# Test_TG21.net
KiCad netlist of a schematic drawn in Altium Designer
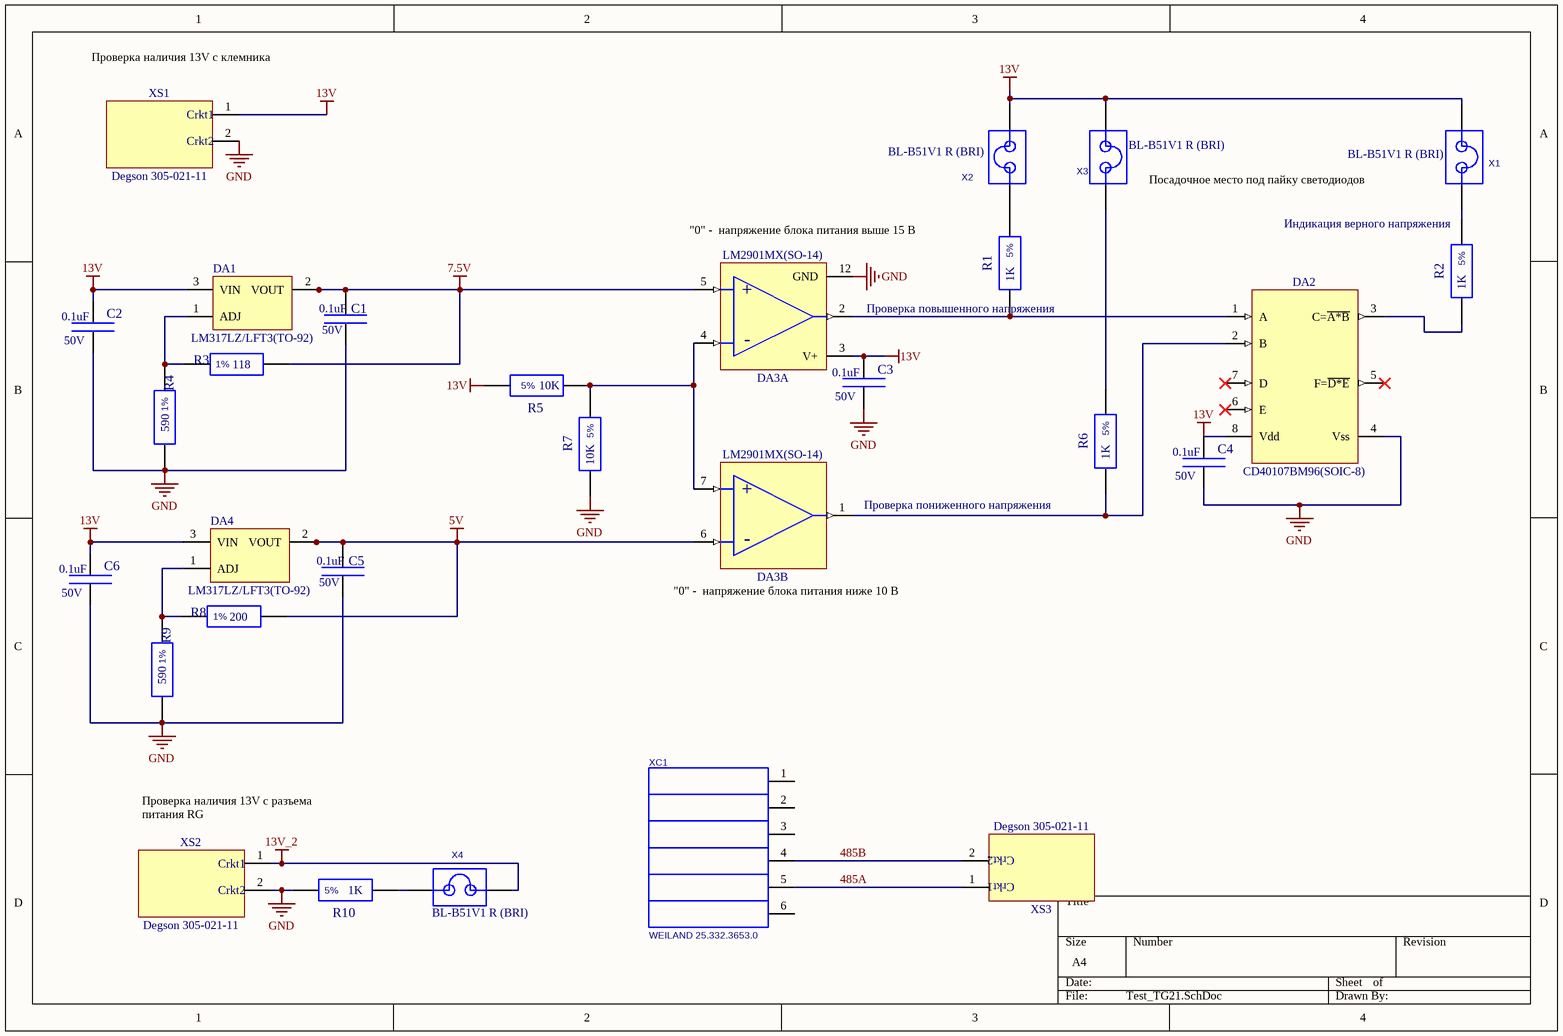
[diagram p0: Test_TG21.SchDoc]

(export (version "E")
  (design (tool "Eeschema 10.0.6"))
  (components
    (comp (ref "C1")
      (value "0.1uF")
      (footprint "CAPC1608X50(0603)")
      (description "C0603")
      (fields (field (name "PARVOLTAGE") "50V") (field (name "Comment") "чип 0603 0.1uF/50V, "))
      (libsource (lib "pass_smd") (part "C0603"))
    )
    (comp (ref "C2")
      (value "0.1uF")
      (footprint "CAPC1608X50(0603)")
      (description "C0603")
      (fields (field (name "PARVOLTAGE") "50V") (field (name "Comment") "чип 0603 0.1uF/50V, "))
      (libsource (lib "pass_smd") (part "C0603"))
    )
    (comp (ref "C3")
      (value "0.1uF")
      (footprint "CAPC1608X50(0603)")
      (description "C0603")
      (fields (field (name "PARVOLTAGE") "50V") (field (name "Comment") "чип 0603 0.1uF/50V, "))
      (libsource (lib "pass_smd") (part "C0603"))
    )
    (comp (ref "C4")
      (value "0.1uF")
      (footprint "CAPC1608X50(0603)")
      (description "C0603")
      (fields (field (name "PARVOLTAGE") "50V") (field (name "Comment") "чип 0603 0.1uF/50V, "))
      (libsource (lib "pass_smd") (part "C0603"))
    )
    (comp (ref "C5")
      (value "0.1uF")
      (footprint "CAPC1608X50(0603)")
      (description "C0603")
      (fields (field (name "PARVOLTAGE") "50V") (field (name "Comment") "чип 0603 0.1uF/50V, "))
      (libsource (lib "pass_smd") (part "C0603"))
    )
    (comp (ref "C6")
      (value "0.1uF")
      (footprint "CAPC1608X50(0603)")
      (description "C0603")
      (fields (field (name "PARVOLTAGE") "50V") (field (name "Comment") "чип 0603 0.1uF/50V, "))
      (libsource (lib "pass_smd") (part "C0603"))
    )
    (comp (ref "DA1")
      (value "LM317LZ/LFT3(TO-92)")
      (footprint "SOT230P700X180-4N(SOT223)_NUM")
      (description "3-Terminal Adjustable Regulator")
      (fields (field (name "CMPPARTNUM") "LM317LZ/LFT3"))
      (libsource (lib "TI") (part "Lm317l-n"))
    )
    (comp (ref "DA2")
      (value "CD40107BM96(SOIC-8)")
      (footprint "SOIC127P600-8N")
      (description "CMOS Dual 2-Input NAND Buffer/Driver")
      (fields (field (name "CMPPARTNUM") "CD40107BM96"))
      (libsource (lib "TI") (part "CD40107B"))
    )
    (comp (ref "DA3")
      (value "LM2901MX(SO-14)")
      (footprint "SOIC127P600X145-14M")
      (fields (field (name "CMPPARTNUM") "LM2901MX"))
      (libsource (lib "TI") (part "LM2901"))
    )
    (comp (ref "DA4")
      (value "LM317LZ/LFT3(TO-92)")
      (footprint "SOT230P700X180-4N(SOT223)_NUM")
      (description "3-Terminal Adjustable Regulator")
      (fields (field (name "CMPPARTNUM") "LM317LZ/LFT3"))
      (libsource (lib "TI") (part "Lm317l-n"))
    )
    (comp (ref "R1")
      (value "1K")
      (footprint "RESC1608X45(0603)")
      (description "R0603")
      (fields (field (name "TOLERANCE") "5%") (field (name "Comment") "чип 0603 1K 5%"))
      (libsource (lib "pass_smd") (part "R0603"))
    )
    (comp (ref "R2")
      (value "1K")
      (footprint "RESC1608X45(0603)")
      (description "R0603")
      (fields (field (name "TOLERANCE") "5%") (field (name "Comment") "чип 0603 1K 5%"))
      (libsource (lib "pass_smd") (part "R0603"))
    )
    (comp (ref "R3")
      (value "118")
      (footprint "RESC1608X45(0603)")
      (description "R0603")
      (fields (field (name "TOLERANCE") "1%") (field (name "Comment") "чип 0603 118 1%"))
      (libsource (lib "pass_smd") (part "R0603"))
    )
    (comp (ref "R4")
      (value "590")
      (footprint "RESC1608X45(0603)")
      (description "R0603")
      (fields (field (name "TOLERANCE") "1%") (field (name "Comment") "чип 0603 590 1%"))
      (libsource (lib "pass_smd") (part "R0603"))
    )
    (comp (ref "R5")
      (value "10K")
      (footprint "RESC1608X45(0603)")
      (description "R0603")
      (fields (field (name "TOLERANCE") "5%") (field (name "Comment") "чип 0603 10K 5%"))
      (libsource (lib "pass_smd") (part "R0603"))
    )
    (comp (ref "R6")
      (value "1K")
      (footprint "RESC1608X45(0603)")
      (description "R0603")
      (fields (field (name "TOLERANCE") "5%") (field (name "Comment") "чип 0603 1K 5%"))
      (libsource (lib "pass_smd") (part "R0603"))
    )
    (comp (ref "R7")
      (value "10K")
      (footprint "RESC1608X45(0603)")
      (description "R0603")
      (fields (field (name "TOLERANCE") "5%") (field (name "Comment") "чип 0603 10K 5%"))
      (libsource (lib "pass_smd") (part "R0603"))
    )
    (comp (ref "R8")
      (value "200")
      (footprint "RESC1608X45(0603)")
      (description "R0603")
      (fields (field (name "TOLERANCE") "1%") (field (name "Comment") "чип 0603 200 1%"))
      (libsource (lib "pass_smd") (part "R0603"))
    )
    (comp (ref "R9")
      (value "590")
      (footprint "RESC1608X45(0603)")
      (description "R0603")
      (fields (field (name "TOLERANCE") "1%") (field (name "Comment") "чип 0603 590 1%"))
      (libsource (lib "pass_smd") (part "R0603"))
    )
    (comp (ref "R10")
      (value "1K")
      (footprint "RESC1608X45(0603)")
      (description "R0603")
      (fields (field (name "TOLERANCE") "5%") (field (name "Comment") "чип 0603 1K 5%"))
      (libsource (lib "pass_smd") (part "R0603"))
    )
    (comp (ref "X1")
      (value "BL-B51V1 R (BRI)")
      (footprint "JMP")
      (description "JMP")
      (libsource (lib "9200mb") (part "JMP"))
    )
    (comp (ref "X2")
      (value "BL-B51V1 R (BRI)")
      (footprint "JMP")
      (description "JMP")
      (libsource (lib "9200mb") (part "JMP"))
    )
    (comp (ref "X3")
      (value "BL-B51V1 R (BRI)")
      (footprint "JMP")
      (description "JMP")
      (libsource (lib "9200mb") (part "JMP"))
    )
    (comp (ref "X4")
      (value "BL-B51V1 R (BRI)")
      (footprint "JMP")
      (description "JMP")
      (libsource (lib "9200mb") (part "JMP"))
    )
    (comp (ref "XC1")
      (value "WEILAND 25.332.3653.0")
      (footprint "WEILAND_25.332.3653.0")
      (description "WEILAND_6PIN_5MM")
      (libsource (lib "connectors") (part "WEILAND_6PIN_5MM"))
    )
    (comp (ref "XS1")
      (value "Degson 305-021-11")
      (footprint "305-021-11")
      (description "Клеммник винтовой, 2-контактный, 5мм, пр мой")
      (fields (field (name "CMPPARTNUM") "305-021-11"))
      (libsource (lib "connectors") (part "305-021-11"))
    )
    (comp (ref "XS2")
      (value "Degson 305-021-11")
      (footprint "305-021-11")
      (description "Клеммник винтовой, 2-контактный, 5мм, пр мой")
      (fields (field (name "CMPPARTNUM") "305-021-11"))
      (libsource (lib "connectors") (part "305-021-11"))
    )
    (comp (ref "XS3")
      (value "Degson 305-021-11")
      (footprint "305-021-11")
      (description "Клеммник винтовой, 2-контактный, 5мм, пр мой")
      (fields (field (name "CMPPARTNUM") "305-021-11"))
      (libsource (lib "") (part "305-021-11_1"))
    )
  )
  (nets
    (net (code "1") (name "/485A") (class "Default")
      (node (ref "XC1") (pin "5") (pinfunction "5_5") (pintype "passive"))
      (node (ref "XS3") (pin "1") (pinfunction "1_1") (pintype "passive"))
    )
    (net (code "2") (name "/485B") (class "Default")
      (node (ref "XC1") (pin "4") (pinfunction "4_4") (pintype "passive"))
      (node (ref "XS3") (pin "2") (pinfunction "2_2") (pintype "passive"))
    )
    (net (code "3") (name "5V") (class "Default")
      (node (ref "C5") (pin "2") (pinfunction "P2_2") (pintype "passive"))
      (node (ref "DA3") (pin "6") (pinfunction "IN-_6") (pintype "input"))
      (node (ref "DA4") (pin "2") (pinfunction "VOUT_2") (pintype "power_in"))
      (node (ref "DA4") (pin "4") (pinfunction "VOUT_4") (pintype "power_in"))
      (node (ref "R8") (pin "1") (pinfunction "1_1") (pintype "passive"))
    )
    (net (code "4") (name "7.5V") (class "Default")
      (node (ref "C1") (pin "2") (pinfunction "P2_2") (pintype "passive"))
      (node (ref "DA1") (pin "2") (pinfunction "VOUT_2") (pintype "power_in"))
      (node (ref "DA1") (pin "4") (pinfunction "VOUT_4") (pintype "power_in"))
      (node (ref "DA3") (pin "5") (pinfunction "IN+_5") (pintype "input"))
      (node (ref "R3") (pin "1") (pinfunction "1_1") (pintype "passive"))
    )
    (net (code "5") (name "13V") (class "Default")
      (node (ref "C2") (pin "2") (pinfunction "P2_2") (pintype "passive"))
      (node (ref "C3") (pin "2") (pinfunction "P2_2") (pintype "passive"))
      (node (ref "C4") (pin "2") (pinfunction "P2_2") (pintype "passive"))
      (node (ref "C6") (pin "2") (pinfunction "P2_2") (pintype "passive"))
      (node (ref "DA1") (pin "3") (pinfunction "VIN_3") (pintype "power_in"))
      (node (ref "DA2") (pin "8") (pinfunction "Vdd_8") (pintype "passive"))
      (node (ref "DA3") (pin "3") (pinfunction "V+_3") (pintype "passive"))
      (node (ref "DA4") (pin "3") (pinfunction "VIN_3") (pintype "power_in"))
      (node (ref "R5") (pin "2") (pinfunction "2_2") (pintype "passive"))
      (node (ref "X1") (pin "1") (pinfunction "1_1") (pintype "passive"))
      (node (ref "X2") (pin "2") (pinfunction "2_2") (pintype "passive"))
      (node (ref "X3") (pin "1") (pinfunction "1_1") (pintype "passive"))
      (node (ref "XS1") (pin "1") (pinfunction "1_1") (pintype "passive"))
    )
    (net (code "6") (name "13V_2") (class "Default")
      (node (ref "X4") (pin "2") (pinfunction "2_2") (pintype "passive"))
      (node (ref "XS2") (pin "1") (pinfunction "1_1") (pintype "passive"))
    )
    (net (code "7") (name "GND") (class "Default")
      (node (ref "C1") (pin "1") (pinfunction "P1_1") (pintype "passive"))
      (node (ref "C2") (pin "1") (pinfunction "P1_1") (pintype "passive"))
      (node (ref "C3") (pin "1") (pinfunction "P1_1") (pintype "passive"))
      (node (ref "C4") (pin "1") (pinfunction "P1_1") (pintype "passive"))
      (node (ref "C5") (pin "1") (pinfunction "P1_1") (pintype "passive"))
      (node (ref "C6") (pin "1") (pinfunction "P1_1") (pintype "passive"))
      (node (ref "DA2") (pin "4") (pinfunction "Vss_4") (pintype "passive"))
      (node (ref "DA3") (pin "12") (pinfunction "GND_12") (pintype "passive"))
      (node (ref "R10") (pin "2") (pinfunction "2_2") (pintype "passive"))
      (node (ref "R4") (pin "1") (pinfunction "1_1") (pintype "passive"))
      (node (ref "R7") (pin "1") (pinfunction "1_1") (pintype "passive"))
      (node (ref "R9") (pin "1") (pinfunction "1_1") (pintype "passive"))
      (node (ref "XS1") (pin "2") (pinfunction "2_2") (pintype "passive"))
      (node (ref "XS2") (pin "2") (pinfunction "2_2") (pintype "passive"))
    )
    (net (code "8") (name "Net-(DA1-ADJ)") (class "Default")
      (node (ref "DA1") (pin "1") (pinfunction "ADJ_1") (pintype "power_in"))
      (node (ref "R3") (pin "2") (pinfunction "2_2") (pintype "passive"))
      (node (ref "R4") (pin "2") (pinfunction "2_2") (pintype "passive"))
    )
    (net (code "9") (name "Net-(DA2-A)") (class "Default")
      (node (ref "DA2") (pin "1") (pinfunction "A_1") (pintype "input"))
      (node (ref "DA3") (pin "2") (pinfunction "Out_2") (pintype "output"))
      (node (ref "R1") (pin "1") (pinfunction "1_1") (pintype "passive"))
    )
    (net (code "10") (name "Net-(DA2-B)") (class "Default")
      (node (ref "DA2") (pin "2") (pinfunction "B_2") (pintype "input"))
      (node (ref "DA3") (pin "1") (pinfunction "Out_1") (pintype "output"))
      (node (ref "R6") (pin "1") (pinfunction "1_1") (pintype "passive"))
    )
    (net (code "11") (name "Net-(DA2-C=~{A*B})") (class "Default")
      (node (ref "DA2") (pin "3") (pinfunction "C=~{A*B}_3") (pintype "output"))
      (node (ref "R2") (pin "1") (pinfunction "1_1") (pintype "passive"))
    )
    (net (code "12") (name "Net-(DA3A-IN-)") (class "Default")
      (node (ref "DA3") (pin "4") (pinfunction "IN-_4") (pintype "input"))
      (node (ref "DA3") (pin "7") (pinfunction "IN+_7") (pintype "input"))
      (node (ref "R5") (pin "1") (pinfunction "1_1") (pintype "passive"))
      (node (ref "R7") (pin "2") (pinfunction "2_2") (pintype "passive"))
    )
    (net (code "13") (name "Net-(DA4-ADJ)") (class "Default")
      (node (ref "DA4") (pin "1") (pinfunction "ADJ_1") (pintype "power_in"))
      (node (ref "R8") (pin "2") (pinfunction "2_2") (pintype "passive"))
      (node (ref "R9") (pin "2") (pinfunction "2_2") (pintype "passive"))
    )
    (net (code "14") (name "Net-(R1-Pad2)") (class "Default")
      (node (ref "R1") (pin "2") (pinfunction "2_2") (pintype "passive"))
      (node (ref "X2") (pin "1") (pinfunction "1_1") (pintype "passive"))
    )
    (net (code "15") (name "Net-(R2-Pad2)") (class "Default")
      (node (ref "R2") (pin "2") (pinfunction "2_2") (pintype "passive"))
      (node (ref "X1") (pin "2") (pinfunction "2_2") (pintype "passive"))
    )
    (net (code "16") (name "Net-(R6-Pad2)") (class "Default")
      (node (ref "R6") (pin "2") (pinfunction "2_2") (pintype "passive"))
      (node (ref "X3") (pin "2") (pinfunction "2_2") (pintype "passive"))
    )
    (net (code "17") (name "Net-(R10-Pad1)") (class "Default")
      (node (ref "R10") (pin "1") (pinfunction "1_1") (pintype "passive"))
      (node (ref "X4") (pin "1") (pinfunction "1_1") (pintype "passive"))
    )
    (net (code "18") (name "unconnected-(DA2-D-Pad7)") (class "Default")
      (node (ref "DA2") (pin "7") (pinfunction "D_7") (pintype "input+no_connect"))
    )
    (net (code "19") (name "unconnected-(DA2-E-Pad6)") (class "Default")
      (node (ref "DA2") (pin "6") (pinfunction "E_6") (pintype "input+no_connect"))
    )
    (net (code "20") (name "unconnected-(DA2-F=~{D*E}-Pad5)") (class "Default")
      (node (ref "DA2") (pin "5") (pinfunction "F=~{D*E}_5") (pintype "output+no_connect"))
    )
    (net (code "21") (name "unconnected-(XC1-Pad1)") (class "Default")
      (node (ref "XC1") (pin "1") (pinfunction "1_1") (pintype "passive"))
    )
    (net (code "22") (name "unconnected-(XC1-Pad2)") (class "Default")
      (node (ref "XC1") (pin "2") (pinfunction "2_2") (pintype "passive"))
    )
    (net (code "23") (name "unconnected-(XC1-Pad3)") (class "Default")
      (node (ref "XC1") (pin "3") (pinfunction "3_3") (pintype "passive"))
    )
    (net (code "24") (name "unconnected-(XC1-Pad6)") (class "Default")
      (node (ref "XC1") (pin "6") (pinfunction "6_6") (pintype "passive"))
    )
  )
)
